# schematics-easyEDA.net
KiCad netlist of a schematic drawn in EasyEDA
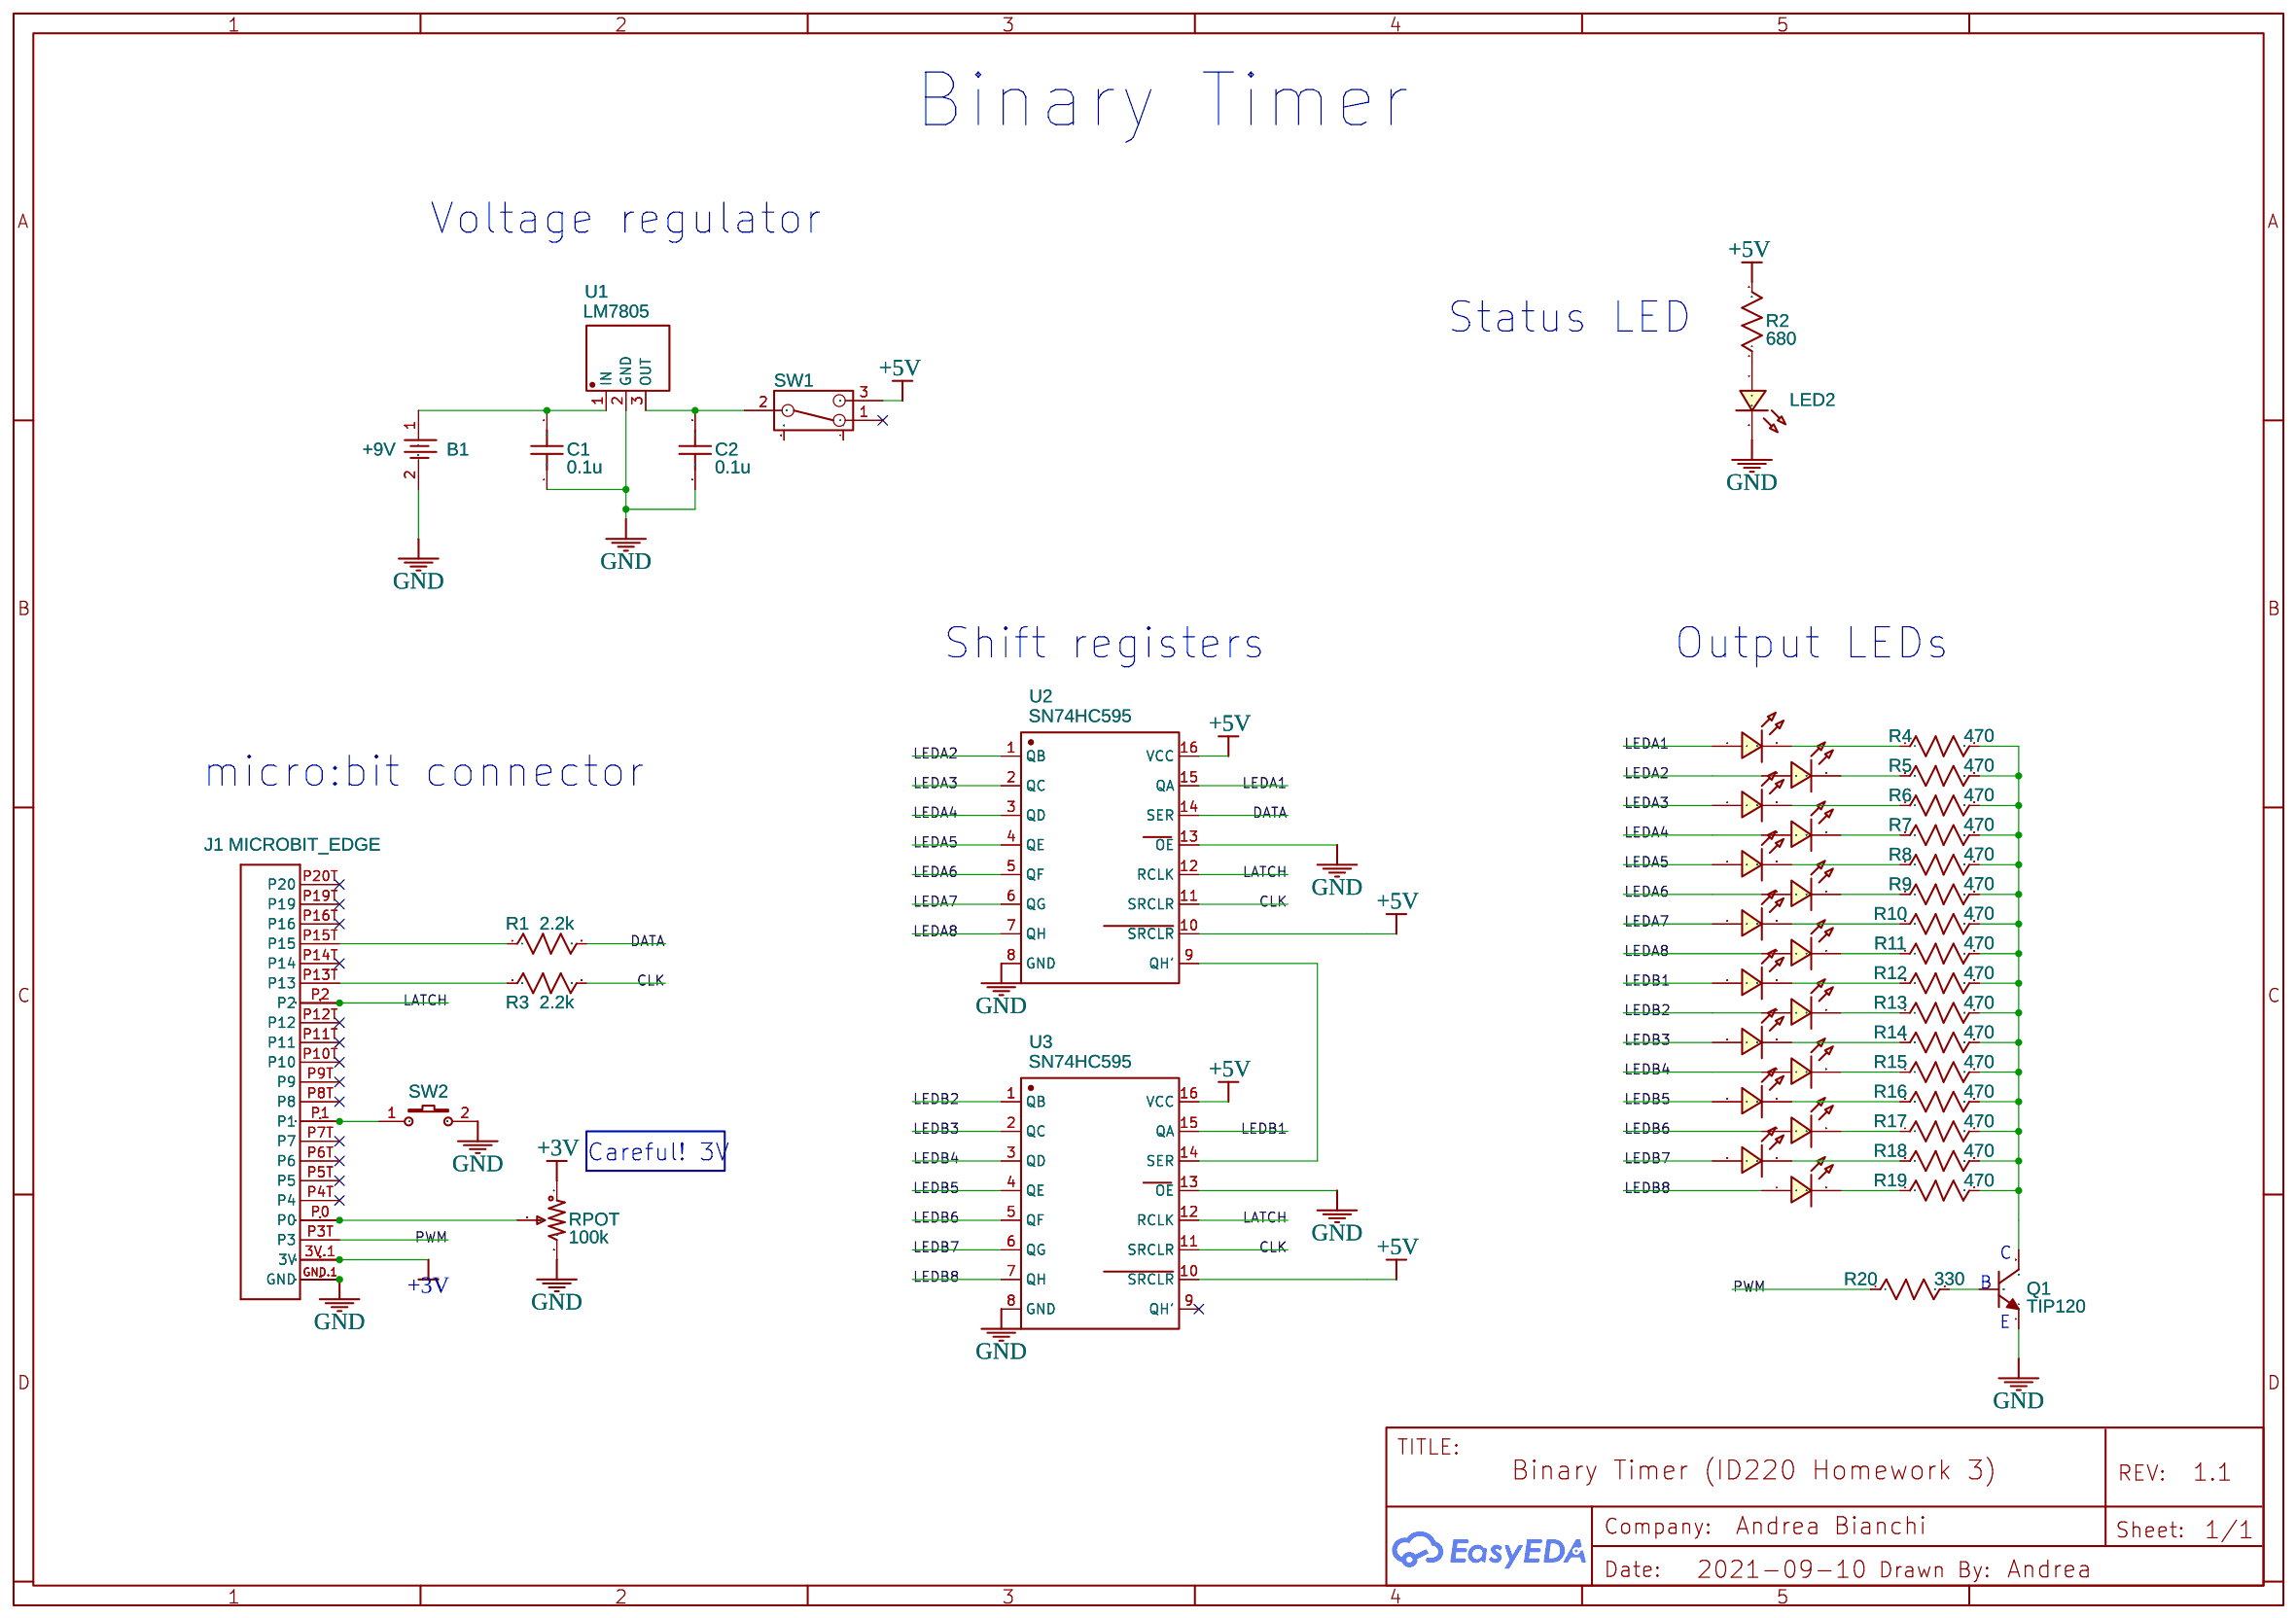
[diagram p0: schematic sheet]

(export (version "E")
  (design (tool "Eeschema 10.0.6"))
  (components
    (comp (ref "1") (value "J1 MICROBIT_EDGE") (libsource (lib "") (part "MICROBIT_EDGE")))
    (comp (ref "B1")
      (value "+9V")
      (fields (field (name "BOM_Manufacturer Part") "CR1220-2") (field (name "BOM_Supplier Part") "C70381"))
      (libsource (lib "") (part "CR1220-2"))
    )
    (comp (ref "C1") (value "0.1u") (libsource (lib "") (part "C_0603_US")))
    (comp (ref "C2") (value "0.1u") (libsource (lib "") (part "C_0603_US")))
    (comp (ref "LED1")
      (value "LED-0603_R")
      (fields
        (field (name "BOM_Manufacturer Part") "19-217/R6C-AL1M2VY/3T")
        (field (name "BOM_Supplier Part") "C72044")
      )
      (libsource (lib "") (part "LED-0603_R"))
    )
    (comp (ref "LED2")
      (value "LED-0603_R")
      (fields
        (field (name "BOM_Manufacturer Part") "19-217/R6C-AL1M2VY/3T")
        (field (name "BOM_Supplier Part") "C72044")
      )
      (libsource (lib "") (part "LED-0603_R_1"))
    )
    (comp (ref "LED3")
      (value "LED-0603_R")
      (fields
        (field (name "BOM_Manufacturer Part") "19-217/R6C-AL1M2VY/3T")
        (field (name "BOM_Supplier Part") "C72044")
      )
      (libsource (lib "") (part "LED-0603_R"))
    )
    (comp (ref "LED4")
      (value "LED-0603_R")
      (fields
        (field (name "BOM_Manufacturer Part") "19-217/R6C-AL1M2VY/3T")
        (field (name "BOM_Supplier Part") "C72044")
      )
      (libsource (lib "") (part "LED-0603_R"))
    )
    (comp (ref "LED5")
      (value "LED-0603_R")
      (fields
        (field (name "BOM_Manufacturer Part") "19-217/R6C-AL1M2VY/3T")
        (field (name "BOM_Supplier Part") "C72044")
      )
      (libsource (lib "") (part "LED-0603_R"))
    )
    (comp (ref "LED6")
      (value "LED-0603_R")
      (fields
        (field (name "BOM_Manufacturer Part") "19-217/R6C-AL1M2VY/3T")
        (field (name "BOM_Supplier Part") "C72044")
      )
      (libsource (lib "") (part "LED-0603_R"))
    )
    (comp (ref "LED7")
      (value "LED-0603_R")
      (fields
        (field (name "BOM_Manufacturer Part") "19-217/R6C-AL1M2VY/3T")
        (field (name "BOM_Supplier Part") "C72044")
      )
      (libsource (lib "") (part "LED-0603_R"))
    )
    (comp (ref "LED8")
      (value "LED-0603_R")
      (fields
        (field (name "BOM_Manufacturer Part") "19-217/R6C-AL1M2VY/3T")
        (field (name "BOM_Supplier Part") "C72044")
      )
      (libsource (lib "") (part "LED-0603_R"))
    )
    (comp (ref "LED9")
      (value "LED-0603_R")
      (fields
        (field (name "BOM_Manufacturer Part") "19-217/R6C-AL1M2VY/3T")
        (field (name "BOM_Supplier Part") "C72044")
      )
      (libsource (lib "") (part "LED-0603_R"))
    )
    (comp (ref "LED10")
      (value "LED-0603_R")
      (fields
        (field (name "BOM_Manufacturer Part") "19-217/R6C-AL1M2VY/3T")
        (field (name "BOM_Supplier Part") "C72044")
      )
      (libsource (lib "") (part "LED-0603_R"))
    )
    (comp (ref "LED11")
      (value "LED-0603_R")
      (fields
        (field (name "BOM_Manufacturer Part") "19-217/R6C-AL1M2VY/3T")
        (field (name "BOM_Supplier Part") "C72044")
      )
      (libsource (lib "") (part "LED-0603_R"))
    )
    (comp (ref "LED12")
      (value "LED-0603_R")
      (fields
        (field (name "BOM_Manufacturer Part") "19-217/R6C-AL1M2VY/3T")
        (field (name "BOM_Supplier Part") "C72044")
      )
      (libsource (lib "") (part "LED-0603_R"))
    )
    (comp (ref "LED13")
      (value "LED-0603_R")
      (fields
        (field (name "BOM_Manufacturer Part") "19-217/R6C-AL1M2VY/3T")
        (field (name "BOM_Supplier Part") "C72044")
      )
      (libsource (lib "") (part "LED-0603_R"))
    )
    (comp (ref "LED14")
      (value "LED-0603_R")
      (fields
        (field (name "BOM_Manufacturer Part") "19-217/R6C-AL1M2VY/3T")
        (field (name "BOM_Supplier Part") "C72044")
      )
      (libsource (lib "") (part "LED-0603_R"))
    )
    (comp (ref "LED15")
      (value "LED-0603_R")
      (fields
        (field (name "BOM_Manufacturer Part") "19-217/R6C-AL1M2VY/3T")
        (field (name "BOM_Supplier Part") "C72044")
      )
      (libsource (lib "") (part "LED-0603_R"))
    )
    (comp (ref "LED16")
      (value "LED-0603_R")
      (fields
        (field (name "BOM_Manufacturer Part") "19-217/R6C-AL1M2VY/3T")
        (field (name "BOM_Supplier Part") "C72044")
      )
      (libsource (lib "") (part "LED-0603_R"))
    )
    (comp (ref "LED17")
      (value "LED-0603_R")
      (fields
        (field (name "BOM_Manufacturer Part") "19-217/R6C-AL1M2VY/3T")
        (field (name "BOM_Supplier Part") "C72044")
      )
      (libsource (lib "") (part "LED-0603_R"))
    )
    (comp (ref "Q1")
      (value "TIP120")
      (fields
        (field (name "BOM_Manufacturer Part") "2n3904S-RTK/PS")
        (field (name "BOM_Supplier Part") "C18536")
      )
      (libsource (lib "") (part "2N3904(SOT-23)"))
    )
    (comp (ref "R1") (value "2.2k") (libsource (lib "") (part "R_0603_US")))
    (comp (ref "R2") (value "680") (libsource (lib "") (part "R_0603_US_1")))
    (comp (ref "R3") (value "2.2k") (libsource (lib "") (part "R_0603_US")))
    (comp (ref "R4") (value "470") (libsource (lib "") (part "R_0603_US")))
    (comp (ref "R5") (value "470") (libsource (lib "") (part "R_0603_US")))
    (comp (ref "R6") (value "470") (libsource (lib "") (part "R_0603_US")))
    (comp (ref "R7") (value "470") (libsource (lib "") (part "R_0603_US")))
    (comp (ref "R8") (value "470") (libsource (lib "") (part "R_0603_US")))
    (comp (ref "R9") (value "470") (libsource (lib "") (part "R_0603_US")))
    (comp (ref "R10") (value "470") (libsource (lib "") (part "R_0603_US")))
    (comp (ref "R11") (value "470") (libsource (lib "") (part "R_0603_US")))
    (comp (ref "R12") (value "470") (libsource (lib "") (part "R_0603_US")))
    (comp (ref "R13") (value "470") (libsource (lib "") (part "R_0603_US")))
    (comp (ref "R14") (value "470") (libsource (lib "") (part "R_0603_US")))
    (comp (ref "R15") (value "470") (libsource (lib "") (part "R_0603_US")))
    (comp (ref "R16") (value "470") (libsource (lib "") (part "R_0603_US")))
    (comp (ref "R17") (value "470") (libsource (lib "") (part "R_0603_US")))
    (comp (ref "R18") (value "470") (libsource (lib "") (part "R_0603_US")))
    (comp (ref "R19") (value "470") (libsource (lib "") (part "R_0603_US")))
    (comp (ref "R20") (value "330") (libsource (lib "") (part "R_0603_US")))
    (comp (ref "RPOT") (value "100k") (libsource (lib "") (part "R_3386P_US")))
    (comp (ref "SW1")
      (value "SK-12D02-VG5")
      (fields (field (name "BOM_Supplier Part") "C136722"))
      (libsource (lib "") (part "SK-12D02-VG5"))
    )
    (comp (ref "SW2")
      (value "K2-3.6×6.1_SMD")
      (fields
        (field (name "BOM_Manufacturer Part") "K2-1107ST-A4SW-06")
        (field (name "BOM_Supplier Part") "C118141")
      )
      (libsource (lib "") (part "K2-3.6×6.1_SMD"))
    )
    (comp (ref "U1")
      (value "LM7805")
      (fields (field (name "BOM_Manufacturer Part") "LM7805CT") (field (name "BOM_Supplier Part") "C22146"))
      (libsource (lib "") (part "LM7805CT"))
    )
    (comp (ref "U2") (value "SN74HC595") (libsource (lib "") (part "SN74HC595")))
    (comp (ref "U3") (value "SN74HC595") (libsource (lib "") (part "SN74HC595")))
  )
  (nets
    (net (code "1") (name "+3V") (class "Default")
      (node (ref "1") (pin "3V.1") (pinfunction "3V_3V.1") (pintype "bidirectional"))
      (node (ref "1") (pin "3V.2") (pinfunction "3V_3V.2") (pintype "bidirectional"))
      (node (ref "1") (pin "3VT") (pinfunction "3V_3VT") (pintype "bidirectional"))
      (node (ref "1") (pin "3VT.1") (pinfunction "3V_3VT.1") (pintype "bidirectional"))
      (node (ref "1") (pin "3VT.2") (pinfunction "3V_3VT.2") (pintype "bidirectional"))
      (node (ref "RPOT") (pin "1") (pinfunction "1_1") (pintype "unspecified"))
    )
    (net (code "2") (name "+5V") (class "Default")
      (node (ref "R2") (pin "2") (pinfunction "2_2") (pintype "unspecified"))
      (node (ref "SW1") (pin "3") (pinfunction "3_3") (pintype "unspecified"))
      (node (ref "U2") (pin "10") (pinfunction "SRCLR_10") (pintype "unspecified"))
      (node (ref "U2") (pin "16") (pinfunction "VCC_16") (pintype "unspecified"))
      (node (ref "U3") (pin "10") (pinfunction "SRCLR_10") (pintype "unspecified"))
      (node (ref "U3") (pin "16") (pinfunction "VCC_16") (pintype "unspecified"))
    )
    (net (code "3") (name "/CLK") (class "Default")
      (node (ref "R3") (pin "2") (pinfunction "2_2") (pintype "unspecified"))
      (node (ref "U2") (pin "11") (pinfunction "SRCLR_11") (pintype "unspecified"))
      (node (ref "U3") (pin "11") (pinfunction "SRCLR_11") (pintype "unspecified"))
    )
    (net (code "4") (name "/DATA") (class "Default")
      (node (ref "R1") (pin "2") (pinfunction "2_2") (pintype "unspecified"))
      (node (ref "U2") (pin "14") (pinfunction "SER_14") (pintype "unspecified"))
    )
    (net (code "5") (name "/LATCH") (class "Default")
      (node (ref "1") (pin "P2") (pinfunction "P2_P2") (pintype "bidirectional"))
      (node (ref "1") (pin "P2.1") (pinfunction "P2_P2.1") (pintype "bidirectional"))
      (node (ref "1") (pin "P2T") (pinfunction "P2_P2T") (pintype "bidirectional"))
      (node (ref "U2") (pin "12") (pinfunction "RCLK_12") (pintype "unspecified"))
      (node (ref "U3") (pin "12") (pinfunction "RCLK_12") (pintype "unspecified"))
    )
    (net (code "6") (name "/LEDA1") (class "Default")
      (node (ref "LED1") (pin "1") (pinfunction "1_1") (pintype "unspecified"))
      (node (ref "U2") (pin "15") (pinfunction "QA_15") (pintype "unspecified"))
    )
    (net (code "7") (name "/LEDA2") (class "Default")
      (node (ref "LED3") (pin "1") (pinfunction "1_1") (pintype "unspecified"))
      (node (ref "U2") (pin "1") (pinfunction "QB_1") (pintype "unspecified"))
    )
    (net (code "8") (name "/LEDA3") (class "Default")
      (node (ref "LED5") (pin "1") (pinfunction "1_1") (pintype "unspecified"))
      (node (ref "U2") (pin "2") (pinfunction "QC_2") (pintype "unspecified"))
    )
    (net (code "9") (name "/LEDA4") (class "Default")
      (node (ref "LED4") (pin "1") (pinfunction "1_1") (pintype "unspecified"))
      (node (ref "U2") (pin "3") (pinfunction "QD_3") (pintype "unspecified"))
    )
    (net (code "10") (name "/LEDA5") (class "Default")
      (node (ref "LED7") (pin "1") (pinfunction "1_1") (pintype "unspecified"))
      (node (ref "U2") (pin "4") (pinfunction "QE_4") (pintype "unspecified"))
    )
    (net (code "11") (name "/LEDA6") (class "Default")
      (node (ref "LED6") (pin "1") (pinfunction "1_1") (pintype "unspecified"))
      (node (ref "U2") (pin "5") (pinfunction "QF_5") (pintype "unspecified"))
    )
    (net (code "12") (name "/LEDA7") (class "Default")
      (node (ref "LED9") (pin "1") (pinfunction "1_1") (pintype "unspecified"))
      (node (ref "U2") (pin "6") (pinfunction "QG_6") (pintype "unspecified"))
    )
    (net (code "13") (name "/LEDA8") (class "Default")
      (node (ref "LED8") (pin "1") (pinfunction "1_1") (pintype "unspecified"))
      (node (ref "U2") (pin "7") (pinfunction "QH_7") (pintype "unspecified"))
    )
    (net (code "14") (name "/LEDB1") (class "Default")
      (node (ref "LED11") (pin "1") (pinfunction "1_1") (pintype "unspecified"))
      (node (ref "U3") (pin "15") (pinfunction "QA_15") (pintype "unspecified"))
    )
    (net (code "15") (name "/LEDB2") (class "Default")
      (node (ref "LED10") (pin "1") (pinfunction "1_1") (pintype "unspecified"))
      (node (ref "U3") (pin "1") (pinfunction "QB_1") (pintype "unspecified"))
    )
    (net (code "16") (name "/LEDB3") (class "Default")
      (node (ref "LED13") (pin "1") (pinfunction "1_1") (pintype "unspecified"))
      (node (ref "U3") (pin "2") (pinfunction "QC_2") (pintype "unspecified"))
    )
    (net (code "17") (name "/LEDB4") (class "Default")
      (node (ref "LED12") (pin "1") (pinfunction "1_1") (pintype "unspecified"))
      (node (ref "U3") (pin "3") (pinfunction "QD_3") (pintype "unspecified"))
    )
    (net (code "18") (name "/LEDB5") (class "Default")
      (node (ref "LED15") (pin "1") (pinfunction "1_1") (pintype "unspecified"))
      (node (ref "U3") (pin "4") (pinfunction "QE_4") (pintype "unspecified"))
    )
    (net (code "19") (name "/LEDB6") (class "Default")
      (node (ref "LED14") (pin "1") (pinfunction "1_1") (pintype "unspecified"))
      (node (ref "U3") (pin "5") (pinfunction "QF_5") (pintype "unspecified"))
    )
    (net (code "20") (name "/LEDB7") (class "Default")
      (node (ref "LED17") (pin "1") (pinfunction "1_1") (pintype "unspecified"))
      (node (ref "U3") (pin "6") (pinfunction "QG_6") (pintype "unspecified"))
    )
    (net (code "21") (name "/LEDB8") (class "Default")
      (node (ref "LED16") (pin "1") (pinfunction "1_1") (pintype "unspecified"))
      (node (ref "U3") (pin "7") (pinfunction "QH_7") (pintype "unspecified"))
    )
    (net (code "22") (name "/PWM") (class "Default")
      (node (ref "1") (pin "P3T") (pinfunction "P3_P3T") (pintype "bidirectional"))
      (node (ref "R20") (pin "1") (pinfunction "1_1") (pintype "unspecified"))
    )
    (net (code "23") (name "GND") (class "Default")
      (node (ref "1") (pin "GND.1") (pinfunction "GND_GND.1") (pintype "bidirectional"))
      (node (ref "1") (pin "GND.2") (pinfunction "GND_GND.2") (pintype "bidirectional"))
      (node (ref "1") (pin "GNDT") (pinfunction "GND_GNDT") (pintype "bidirectional"))
      (node (ref "1") (pin "GNDT.1") (pinfunction "GND_GNDT.1") (pintype "bidirectional"))
      (node (ref "1") (pin "GNDT.2") (pinfunction "GND_GNDT.2") (pintype "bidirectional"))
      (node (ref "B1") (pin "2") (pinfunction "2_2") (pintype "input"))
      (node (ref "C1") (pin "1") (pinfunction "1_1") (pintype "unspecified"))
      (node (ref "C2") (pin "1") (pinfunction "1_1") (pintype "unspecified"))
      (node (ref "LED2") (pin "2") (pinfunction "2_2") (pintype "unspecified"))
      (node (ref "Q1") (pin "1") (pinfunction "E_1") (pintype "input"))
      (node (ref "RPOT") (pin "3") (pinfunction "3_3") (pintype "unspecified"))
      (node (ref "SW2") (pin "2") (pinfunction "2_2") (pintype "unspecified"))
      (node (ref "U1") (pin "2") (pinfunction "GND_2") (pintype "unspecified"))
      (node (ref "U2") (pin "13") (pinfunction "OE_13") (pintype "unspecified"))
      (node (ref "U2") (pin "8") (pinfunction "GND_8") (pintype "unspecified"))
      (node (ref "U3") (pin "13") (pinfunction "OE_13") (pintype "unspecified"))
      (node (ref "U3") (pin "8") (pinfunction "GND_8") (pintype "unspecified"))
    )
    (net (code "24") (name "Net-(1-P0-PadP0,1)") (class "Default")
      (node (ref "1") (pin "P0") (pinfunction "P0_P0") (pintype "bidirectional"))
      (node (ref "1") (pin "P0,1") (pinfunction "P0_P0,1") (pintype "bidirectional"))
      (node (ref "1") (pin "P0T") (pinfunction "P0_P0T") (pintype "bidirectional"))
      (node (ref "RPOT") (pin "2") (pinfunction "2_2") (pintype "unspecified"))
    )
    (net (code "25") (name "Net-(1-P1-PadP1.1)") (class "Default")
      (node (ref "1") (pin "P1") (pinfunction "P1_P1") (pintype "bidirectional"))
      (node (ref "1") (pin "P1.1") (pinfunction "P1_P1.1") (pintype "bidirectional"))
      (node (ref "1") (pin "P1T") (pinfunction "P1_P1T") (pintype "bidirectional"))
      (node (ref "SW2") (pin "1") (pinfunction "1_1") (pintype "unspecified"))
    )
    (net (code "26") (name "Net-(1-P13)") (class "Default")
      (node (ref "1") (pin "P13T") (pinfunction "P13_P13T") (pintype "bidirectional"))
      (node (ref "R3") (pin "1") (pinfunction "1_1") (pintype "unspecified"))
    )
    (net (code "27") (name "Net-(1-P15)") (class "Default")
      (node (ref "1") (pin "P15T") (pinfunction "P15_P15T") (pintype "bidirectional"))
      (node (ref "R1") (pin "1") (pinfunction "1_1") (pintype "unspecified"))
    )
    (net (code "28") (name "Net-(LED1-Pad2)") (class "Default")
      (node (ref "LED1") (pin "2") (pinfunction "2_2") (pintype "unspecified"))
      (node (ref "R4") (pin "1") (pinfunction "1_1") (pintype "unspecified"))
    )
    (net (code "29") (name "Net-(LED2-Pad1)") (class "Default")
      (node (ref "LED2") (pin "1") (pinfunction "1_1") (pintype "unspecified"))
      (node (ref "R2") (pin "1") (pinfunction "1_1") (pintype "unspecified"))
    )
    (net (code "30") (name "Net-(LED3-Pad2)") (class "Default")
      (node (ref "LED3") (pin "2") (pinfunction "2_2") (pintype "unspecified"))
      (node (ref "R5") (pin "1") (pinfunction "1_1") (pintype "unspecified"))
    )
    (net (code "31") (name "Net-(LED4-Pad2)") (class "Default")
      (node (ref "LED4") (pin "2") (pinfunction "2_2") (pintype "unspecified"))
      (node (ref "R7") (pin "1") (pinfunction "1_1") (pintype "unspecified"))
    )
    (net (code "32") (name "Net-(LED5-Pad2)") (class "Default")
      (node (ref "LED5") (pin "2") (pinfunction "2_2") (pintype "unspecified"))
      (node (ref "R6") (pin "1") (pinfunction "1_1") (pintype "unspecified"))
    )
    (net (code "33") (name "Net-(LED6-Pad2)") (class "Default")
      (node (ref "LED6") (pin "2") (pinfunction "2_2") (pintype "unspecified"))
      (node (ref "R9") (pin "1") (pinfunction "1_1") (pintype "unspecified"))
    )
    (net (code "34") (name "Net-(LED7-Pad2)") (class "Default")
      (node (ref "LED7") (pin "2") (pinfunction "2_2") (pintype "unspecified"))
      (node (ref "R8") (pin "1") (pinfunction "1_1") (pintype "unspecified"))
    )
    (net (code "35") (name "Net-(LED8-Pad2)") (class "Default")
      (node (ref "LED8") (pin "2") (pinfunction "2_2") (pintype "unspecified"))
      (node (ref "R11") (pin "1") (pinfunction "1_1") (pintype "unspecified"))
    )
    (net (code "36") (name "Net-(LED9-Pad2)") (class "Default")
      (node (ref "LED9") (pin "2") (pinfunction "2_2") (pintype "unspecified"))
      (node (ref "R10") (pin "1") (pinfunction "1_1") (pintype "unspecified"))
    )
    (net (code "37") (name "Net-(LED10-Pad2)") (class "Default")
      (node (ref "LED10") (pin "2") (pinfunction "2_2") (pintype "unspecified"))
      (node (ref "R13") (pin "1") (pinfunction "1_1") (pintype "unspecified"))
    )
    (net (code "38") (name "Net-(LED11-Pad2)") (class "Default")
      (node (ref "LED11") (pin "2") (pinfunction "2_2") (pintype "unspecified"))
      (node (ref "R12") (pin "1") (pinfunction "1_1") (pintype "unspecified"))
    )
    (net (code "39") (name "Net-(LED12-Pad2)") (class "Default")
      (node (ref "LED12") (pin "2") (pinfunction "2_2") (pintype "unspecified"))
      (node (ref "R15") (pin "1") (pinfunction "1_1") (pintype "unspecified"))
    )
    (net (code "40") (name "Net-(LED13-Pad2)") (class "Default")
      (node (ref "LED13") (pin "2") (pinfunction "2_2") (pintype "unspecified"))
      (node (ref "R14") (pin "1") (pinfunction "1_1") (pintype "unspecified"))
    )
    (net (code "41") (name "Net-(LED14-Pad2)") (class "Default")
      (node (ref "LED14") (pin "2") (pinfunction "2_2") (pintype "unspecified"))
      (node (ref "R17") (pin "1") (pinfunction "1_1") (pintype "unspecified"))
    )
    (net (code "42") (name "Net-(LED15-Pad2)") (class "Default")
      (node (ref "LED15") (pin "2") (pinfunction "2_2") (pintype "unspecified"))
      (node (ref "R16") (pin "1") (pinfunction "1_1") (pintype "unspecified"))
    )
    (net (code "43") (name "Net-(LED16-Pad2)") (class "Default")
      (node (ref "LED16") (pin "2") (pinfunction "2_2") (pintype "unspecified"))
      (node (ref "R19") (pin "1") (pinfunction "1_1") (pintype "unspecified"))
    )
    (net (code "44") (name "Net-(LED17-Pad2)") (class "Default")
      (node (ref "LED17") (pin "2") (pinfunction "2_2") (pintype "unspecified"))
      (node (ref "R18") (pin "1") (pinfunction "1_1") (pintype "unspecified"))
    )
    (net (code "45") (name "Net-(Q1-B)") (class "Default")
      (node (ref "Q1") (pin "2") (pinfunction "B_2") (pintype "input"))
      (node (ref "R20") (pin "2") (pinfunction "2_2") (pintype "unspecified"))
    )
    (net (code "46") (name "Net-(Q1-C)") (class "Default")
      (node (ref "Q1") (pin "3") (pinfunction "C_3") (pintype "input"))
      (node (ref "R10") (pin "2") (pinfunction "2_2") (pintype "unspecified"))
      (node (ref "R11") (pin "2") (pinfunction "2_2") (pintype "unspecified"))
      (node (ref "R12") (pin "2") (pinfunction "2_2") (pintype "unspecified"))
      (node (ref "R13") (pin "2") (pinfunction "2_2") (pintype "unspecified"))
      (node (ref "R14") (pin "2") (pinfunction "2_2") (pintype "unspecified"))
      (node (ref "R15") (pin "2") (pinfunction "2_2") (pintype "unspecified"))
      (node (ref "R16") (pin "2") (pinfunction "2_2") (pintype "unspecified"))
      (node (ref "R17") (pin "2") (pinfunction "2_2") (pintype "unspecified"))
      (node (ref "R18") (pin "2") (pinfunction "2_2") (pintype "unspecified"))
      (node (ref "R19") (pin "2") (pinfunction "2_2") (pintype "unspecified"))
      (node (ref "R4") (pin "2") (pinfunction "2_2") (pintype "unspecified"))
      (node (ref "R5") (pin "2") (pinfunction "2_2") (pintype "unspecified"))
      (node (ref "R6") (pin "2") (pinfunction "2_2") (pintype "unspecified"))
      (node (ref "R7") (pin "2") (pinfunction "2_2") (pintype "unspecified"))
      (node (ref "R8") (pin "2") (pinfunction "2_2") (pintype "unspecified"))
      (node (ref "R9") (pin "2") (pinfunction "2_2") (pintype "unspecified"))
    )
    (net (code "47") (name "Net-(U1-IN)") (class "Default")
      (node (ref "B1") (pin "1") (pinfunction "1_1") (pintype "input"))
      (node (ref "C1") (pin "2") (pinfunction "2_2") (pintype "unspecified"))
      (node (ref "U1") (pin "1") (pinfunction "IN_1") (pintype "unspecified"))
    )
    (net (code "48") (name "Net-(U1-OUT)") (class "Default")
      (node (ref "C2") (pin "2") (pinfunction "2_2") (pintype "unspecified"))
      (node (ref "SW1") (pin "2") (pinfunction "2_2") (pintype "unspecified"))
      (node (ref "U1") (pin "3") (pinfunction "OUT_3") (pintype "unspecified"))
    )
    (net (code "49") (name "Net-(U2-QH')") (class "Default")
      (node (ref "U2") (pin "9") (pinfunction "QH'_9") (pintype "unspecified"))
      (node (ref "U3") (pin "14") (pinfunction "SER_14") (pintype "unspecified"))
    )
    (net (code "50") (name "unconnected-(1-P4-PadP4T)") (class "Default")
      (node (ref "1") (pin "P4T") (pinfunction "P4_P4T") (pintype "bidirectional+no_connect"))
    )
    (net (code "51") (name "unconnected-(1-P5-PadP5T)") (class "Default")
      (node (ref "1") (pin "P5T") (pinfunction "P5_P5T") (pintype "bidirectional+no_connect"))
    )
    (net (code "52") (name "unconnected-(1-P6-PadP6T)") (class "Default")
      (node (ref "1") (pin "P6T") (pinfunction "P6_P6T") (pintype "bidirectional+no_connect"))
    )
    (net (code "53") (name "unconnected-(1-P7-PadP7T)") (class "Default")
      (node (ref "1") (pin "P7T") (pinfunction "P7_P7T") (pintype "bidirectional+no_connect"))
    )
    (net (code "54") (name "unconnected-(1-P8-PadP8T)") (class "Default")
      (node (ref "1") (pin "P8T") (pinfunction "P8_P8T") (pintype "bidirectional+no_connect"))
    )
    (net (code "55") (name "unconnected-(1-P9-PadP9T)") (class "Default")
      (node (ref "1") (pin "P9T") (pinfunction "P9_P9T") (pintype "bidirectional+no_connect"))
    )
    (net (code "56") (name "unconnected-(1-P10-PadP10T)") (class "Default")
      (node (ref "1") (pin "P10T") (pinfunction "P10_P10T") (pintype "bidirectional+no_connect"))
    )
    (net (code "57") (name "unconnected-(1-P11-PadP11T)") (class "Default")
      (node (ref "1") (pin "P11T") (pinfunction "P11_P11T") (pintype "bidirectional+no_connect"))
    )
    (net (code "58") (name "unconnected-(1-P12-PadP12T)") (class "Default")
      (node (ref "1") (pin "P12T") (pinfunction "P12_P12T") (pintype "bidirectional+no_connect"))
    )
    (net (code "59") (name "unconnected-(1-P14-PadP14T)") (class "Default")
      (node (ref "1") (pin "P14T") (pinfunction "P14_P14T") (pintype "bidirectional+no_connect"))
    )
    (net (code "60") (name "unconnected-(1-P16-PadP16T)") (class "Default")
      (node (ref "1") (pin "P16T") (pinfunction "P16_P16T") (pintype "bidirectional+no_connect"))
    )
    (net (code "61") (name "unconnected-(1-P19-PadP19T)") (class "Default")
      (node (ref "1") (pin "P19T") (pinfunction "P19_P19T") (pintype "bidirectional+no_connect"))
    )
    (net (code "62") (name "unconnected-(1-P20-PadP20T)") (class "Default")
      (node (ref "1") (pin "P20T") (pinfunction "P20_P20T") (pintype "bidirectional+no_connect"))
    )
    (net (code "63") (name "unconnected-(SW1-Pad1)") (class "Default")
      (node (ref "SW1") (pin "1") (pinfunction "1_1") (pintype "unspecified+no_connect"))
    )
    (net (code "64") (name "unconnected-(SW1-Pad4)") (class "Default")
      (node (ref "SW1") (pin "4") (pinfunction "4_4") (pintype "unspecified"))
    )
    (net (code "65") (name "unconnected-(SW1-Pad5)") (class "Default")
      (node (ref "SW1") (pin "5") (pinfunction "5_5") (pintype "unspecified"))
    )
    (net (code "66") (name "unconnected-(U3-QH'-Pad9)") (class "Default")
      (node (ref "U3") (pin "9") (pinfunction "QH'_9") (pintype "unspecified+no_connect"))
    )
  )
)
